# TIC_TAC_PCB1.net
KiCad netlist of a schematic drawn in EAGLE
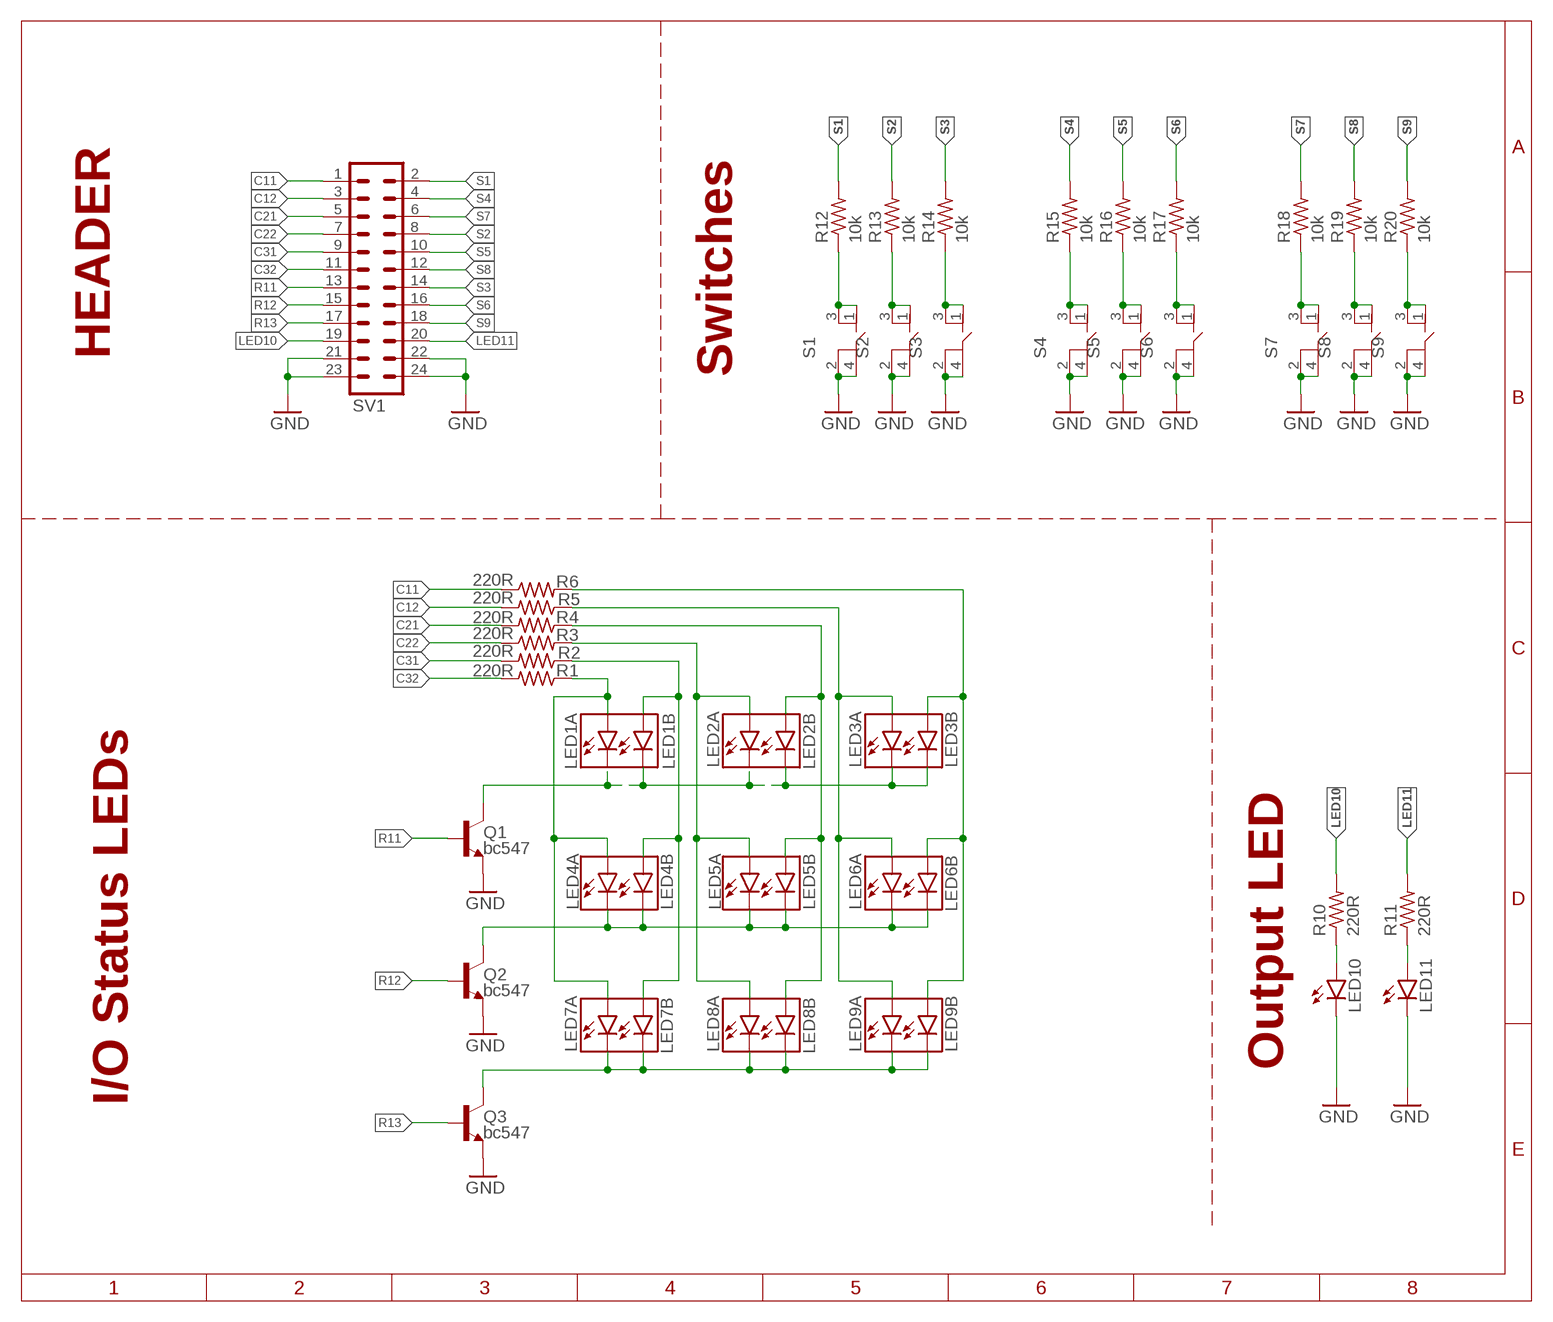
[diagram p0: schematic, sheet 1]

(export (version "E")
  (design (tool "Eeschema 10.0.6"))
  (components
    (comp (ref "LED1A")
      (value "LEDSML0805")
      (footprint "eagle-import:SML0805")
      (libsource (lib "eagle-import") (part "LEDSML0805"))
    )
    (comp (ref "LED1B")
      (value "LEDSML0805")
      (footprint "eagle-import:SML0805")
      (libsource (lib "eagle-import") (part "LEDSML0805"))
    )
    (comp (ref "LED2A")
      (value "LEDSML0805")
      (footprint "eagle-import:SML0805")
      (libsource (lib "eagle-import") (part "LEDSML0805"))
    )
    (comp (ref "LED2B")
      (value "LEDSML0805")
      (footprint "eagle-import:SML0805")
      (libsource (lib "eagle-import") (part "LEDSML0805"))
    )
    (comp (ref "LED3A")
      (value "LEDSML0805")
      (footprint "eagle-import:SML0805")
      (libsource (lib "eagle-import") (part "LEDSML0805"))
    )
    (comp (ref "LED3B")
      (value "LEDSML0805")
      (footprint "eagle-import:SML0805")
      (libsource (lib "eagle-import") (part "LEDSML0805"))
    )
    (comp (ref "LED4A")
      (value "LEDSML0805")
      (footprint "eagle-import:SML0805")
      (libsource (lib "eagle-import") (part "LEDSML0805"))
    )
    (comp (ref "LED4B")
      (value "LEDSML0805")
      (footprint "eagle-import:SML0805")
      (libsource (lib "eagle-import") (part "LEDSML0805"))
    )
    (comp (ref "LED5A")
      (value "LEDSML0805")
      (footprint "eagle-import:SML0805")
      (libsource (lib "eagle-import") (part "LEDSML0805"))
    )
    (comp (ref "LED5B")
      (value "LEDSML0805")
      (footprint "eagle-import:SML0805")
      (libsource (lib "eagle-import") (part "LEDSML0805"))
    )
    (comp (ref "LED6A")
      (value "LEDSML0805")
      (footprint "eagle-import:SML0805")
      (libsource (lib "eagle-import") (part "LEDSML0805"))
    )
    (comp (ref "LED6B")
      (value "LEDSML0805")
      (footprint "eagle-import:SML0805")
      (libsource (lib "eagle-import") (part "LEDSML0805"))
    )
    (comp (ref "LED7A")
      (value "LEDSML0805")
      (footprint "eagle-import:SML0805")
      (libsource (lib "eagle-import") (part "LEDSML0805"))
    )
    (comp (ref "LED7B")
      (value "LEDSML0805")
      (footprint "eagle-import:SML0805")
      (libsource (lib "eagle-import") (part "LEDSML0805"))
    )
    (comp (ref "LED8A")
      (value "LEDSML0805")
      (footprint "eagle-import:SML0805")
      (libsource (lib "eagle-import") (part "LEDSML0805"))
    )
    (comp (ref "LED8B")
      (value "LEDSML0805")
      (footprint "eagle-import:SML0805")
      (libsource (lib "eagle-import") (part "LEDSML0805"))
    )
    (comp (ref "LED9A")
      (value "LEDSML0805")
      (footprint "eagle-import:SML0805")
      (libsource (lib "eagle-import") (part "LEDSML0805"))
    )
    (comp (ref "LED9B")
      (value "LEDSML0805")
      (footprint "eagle-import:SML0805")
      (libsource (lib "eagle-import") (part "LEDSML0805"))
    )
    (comp (ref "LED10")
      (value "LEDSMT1206")
      (footprint "eagle-import:1206")
      (libsource (lib "eagle-import") (part "LEDSMT1206"))
    )
    (comp (ref "LED11")
      (value "LEDSMT1206")
      (footprint "eagle-import:1206")
      (libsource (lib "eagle-import") (part "LEDSMT1206"))
    )
    (comp (ref "Q1")
      (value "bc547")
      (footprint "eagle-import:SOT23-3")
      (libsource (lib "eagle-import") (part "TRANS_NPN-MMBT2222AL"))
    )
    (comp (ref "Q2")
      (value "bc547")
      (footprint "eagle-import:SOT23-3")
      (libsource (lib "eagle-import") (part "TRANS_NPN-MMBT2222AL"))
    )
    (comp (ref "Q3")
      (value "bc547")
      (footprint "eagle-import:SOT23-3")
      (libsource (lib "eagle-import") (part "TRANS_NPN-MMBT2222AL"))
    )
    (comp (ref "R1")
      (value "220R")
      (footprint "eagle-import:M0805")
      (libsource (lib "eagle-import") (part "R-US_M0805"))
    )
    (comp (ref "R2")
      (value "220R")
      (footprint "eagle-import:M0805")
      (libsource (lib "eagle-import") (part "R-US_M0805"))
    )
    (comp (ref "R3")
      (value "220R")
      (footprint "eagle-import:M0805")
      (libsource (lib "eagle-import") (part "R-US_M0805"))
    )
    (comp (ref "R4")
      (value "220R")
      (footprint "eagle-import:M0805")
      (libsource (lib "eagle-import") (part "R-US_M0805"))
    )
    (comp (ref "R5")
      (value "220R")
      (footprint "eagle-import:M0805")
      (libsource (lib "eagle-import") (part "R-US_M0805"))
    )
    (comp (ref "R6")
      (value "220R")
      (footprint "eagle-import:M0805")
      (libsource (lib "eagle-import") (part "R-US_M0805"))
    )
    (comp (ref "R10")
      (value "220R")
      (footprint "eagle-import:M0805")
      (libsource (lib "eagle-import") (part "R-US_M0805"))
    )
    (comp (ref "R11")
      (value "220R")
      (footprint "eagle-import:M0805")
      (libsource (lib "eagle-import") (part "R-US_M0805"))
    )
    (comp (ref "R12")
      (value "10k")
      (footprint "eagle-import:M0805")
      (libsource (lib "eagle-import") (part "R-US_M0805"))
    )
    (comp (ref "R13")
      (value "10k")
      (footprint "eagle-import:M0805")
      (libsource (lib "eagle-import") (part "R-US_M0805"))
    )
    (comp (ref "R14")
      (value "10k")
      (footprint "eagle-import:M0805")
      (libsource (lib "eagle-import") (part "R-US_M0805"))
    )
    (comp (ref "R15")
      (value "10k")
      (footprint "eagle-import:M0805")
      (libsource (lib "eagle-import") (part "R-US_M0805"))
    )
    (comp (ref "R16")
      (value "10k")
      (footprint "eagle-import:M0805")
      (libsource (lib "eagle-import") (part "R-US_M0805"))
    )
    (comp (ref "R17")
      (value "10k")
      (footprint "eagle-import:M0805")
      (libsource (lib "eagle-import") (part "R-US_M0805"))
    )
    (comp (ref "R18")
      (value "10k")
      (footprint "eagle-import:M0805")
      (libsource (lib "eagle-import") (part "R-US_M0805"))
    )
    (comp (ref "R19")
      (value "10k")
      (footprint "eagle-import:M0805")
      (libsource (lib "eagle-import") (part "R-US_M0805"))
    )
    (comp (ref "R20")
      (value "10k")
      (footprint "eagle-import:M0805")
      (libsource (lib "eagle-import") (part "R-US_M0805"))
    )
    (comp (ref "S1")
      (value "TS04-66-95-BK-100-SMT")
      (footprint "eagle-import:SW_TS04-66-95-BK-100-SMT")
      (fields (field (name "MF") "CUI Devices"))
      (libsource (lib "eagle-import") (part "TS04-66-95-BK-100-SMT"))
    )
    (comp (ref "S2")
      (value "TS04-66-95-BK-100-SMT")
      (footprint "eagle-import:SW_TS04-66-95-BK-100-SMT")
      (fields (field (name "MF") "CUI Devices"))
      (libsource (lib "eagle-import") (part "TS04-66-95-BK-100-SMT"))
    )
    (comp (ref "S3")
      (value "TS04-66-95-BK-100-SMT")
      (footprint "eagle-import:SW_TS04-66-95-BK-100-SMT")
      (fields (field (name "MF") "CUI Devices"))
      (libsource (lib "eagle-import") (part "TS04-66-95-BK-100-SMT"))
    )
    (comp (ref "S4")
      (value "TS04-66-95-BK-100-SMT")
      (footprint "eagle-import:SW_TS04-66-95-BK-100-SMT")
      (fields (field (name "MF") "CUI Devices"))
      (libsource (lib "eagle-import") (part "TS04-66-95-BK-100-SMT"))
    )
    (comp (ref "S5")
      (value "TS04-66-95-BK-100-SMT")
      (footprint "eagle-import:SW_TS04-66-95-BK-100-SMT")
      (fields (field (name "MF") "CUI Devices"))
      (libsource (lib "eagle-import") (part "TS04-66-95-BK-100-SMT"))
    )
    (comp (ref "S6")
      (value "TS04-66-95-BK-100-SMT")
      (footprint "eagle-import:SW_TS04-66-95-BK-100-SMT")
      (fields (field (name "MF") "CUI Devices"))
      (libsource (lib "eagle-import") (part "TS04-66-95-BK-100-SMT"))
    )
    (comp (ref "S7")
      (value "TS04-66-95-BK-100-SMT")
      (footprint "eagle-import:SW_TS04-66-95-BK-100-SMT")
      (fields (field (name "MF") "CUI Devices"))
      (libsource (lib "eagle-import") (part "TS04-66-95-BK-100-SMT"))
    )
    (comp (ref "S8")
      (value "TS04-66-95-BK-100-SMT")
      (footprint "eagle-import:SW_TS04-66-95-BK-100-SMT")
      (fields (field (name "MF") "CUI Devices"))
      (libsource (lib "eagle-import") (part "TS04-66-95-BK-100-SMT"))
    )
    (comp (ref "S9")
      (value "TS04-66-95-BK-100-SMT")
      (footprint "eagle-import:SW_TS04-66-95-BK-100-SMT")
      (fields (field (name "MF") "CUI Devices"))
      (libsource (lib "eagle-import") (part "TS04-66-95-BK-100-SMT"))
    )
    (comp (ref "SV1")
      (value "MA12-2")
      (footprint "eagle-import:MA12-2")
      (libsource (lib "eagle-import") (part "MA12-2"))
    )
  )
  (nets
    (net (code "1") (name "C11") (class "Default")
      (node (ref "R6") (pin "1") (pinfunction "1_1") (pintype "passive"))
      (node (ref "SV1") (pin "1") (pinfunction "1_1") (pintype "passive"))
    )
    (net (code "2") (name "C12") (class "Default")
      (node (ref "R5") (pin "2") (pinfunction "2_2") (pintype "passive"))
      (node (ref "SV1") (pin "3") (pinfunction "3_3") (pintype "passive"))
    )
    (net (code "3") (name "C21") (class "Default")
      (node (ref "R4") (pin "2") (pinfunction "2_2") (pintype "passive"))
      (node (ref "SV1") (pin "5") (pinfunction "5_5") (pintype "passive"))
    )
    (net (code "4") (name "C22") (class "Default")
      (node (ref "R3") (pin "1") (pinfunction "1_1") (pintype "passive"))
      (node (ref "SV1") (pin "7") (pinfunction "7_7") (pintype "passive"))
    )
    (net (code "5") (name "C31") (class "Default")
      (node (ref "R2") (pin "2") (pinfunction "2_2") (pintype "passive"))
      (node (ref "SV1") (pin "9") (pinfunction "9_9") (pintype "passive"))
    )
    (net (code "6") (name "C32") (class "Default")
      (node (ref "R1") (pin "2") (pinfunction "2_2") (pintype "passive"))
      (node (ref "SV1") (pin "11") (pinfunction "11_11") (pintype "passive"))
    )
    (net (code "7") (name "GND") (class "Default")
      (node (ref "LED10") (pin "C") (pinfunction "C_C") (pintype "passive"))
      (node (ref "LED11") (pin "C") (pinfunction "C_C") (pintype "passive"))
      (node (ref "Q1") (pin "2") (pinfunction "E_2") (pintype "passive"))
      (node (ref "Q2") (pin "2") (pinfunction "E_2") (pintype "passive"))
      (node (ref "Q3") (pin "2") (pinfunction "E_2") (pintype "passive"))
      (node (ref "S1") (pin "2") (pinfunction "3_2") (pintype "passive"))
      (node (ref "S1") (pin "4") (pinfunction "4_4") (pintype "passive"))
      (node (ref "S2") (pin "2") (pinfunction "3_2") (pintype "passive"))
      (node (ref "S2") (pin "4") (pinfunction "4_4") (pintype "passive"))
      (node (ref "S3") (pin "2") (pinfunction "3_2") (pintype "passive"))
      (node (ref "S3") (pin "4") (pinfunction "4_4") (pintype "passive"))
      (node (ref "S4") (pin "2") (pinfunction "3_2") (pintype "passive"))
      (node (ref "S4") (pin "4") (pinfunction "4_4") (pintype "passive"))
      (node (ref "S5") (pin "2") (pinfunction "3_2") (pintype "passive"))
      (node (ref "S5") (pin "4") (pinfunction "4_4") (pintype "passive"))
      (node (ref "S6") (pin "2") (pinfunction "3_2") (pintype "passive"))
      (node (ref "S6") (pin "4") (pinfunction "4_4") (pintype "passive"))
      (node (ref "S7") (pin "2") (pinfunction "3_2") (pintype "passive"))
      (node (ref "S7") (pin "4") (pinfunction "4_4") (pintype "passive"))
      (node (ref "S8") (pin "2") (pinfunction "3_2") (pintype "passive"))
      (node (ref "S8") (pin "4") (pinfunction "4_4") (pintype "passive"))
      (node (ref "S9") (pin "2") (pinfunction "3_2") (pintype "passive"))
      (node (ref "S9") (pin "4") (pinfunction "4_4") (pintype "passive"))
      (node (ref "SV1") (pin "21") (pinfunction "21_21") (pintype "passive"))
      (node (ref "SV1") (pin "22") (pinfunction "22_22") (pintype "passive"))
      (node (ref "SV1") (pin "23") (pinfunction "23_23") (pintype "passive"))
      (node (ref "SV1") (pin "24") (pinfunction "24_24") (pintype "passive"))
    )
    (net (code "8") (name "LED10") (class "Default")
      (node (ref "R10") (pin "2") (pinfunction "2_2") (pintype "passive"))
      (node (ref "SV1") (pin "19") (pinfunction "19_19") (pintype "passive"))
    )
    (net (code "9") (name "LED11") (class "Default")
      (node (ref "R11") (pin "2") (pinfunction "2_2") (pintype "passive"))
      (node (ref "SV1") (pin "20") (pinfunction "20_20") (pintype "passive"))
    )
    (net (code "10") (name "Net-(LED1A-PadA)") (class "Default")
      (node (ref "LED1A") (pin "A") (pinfunction "A_A") (pintype "passive"))
      (node (ref "LED4A") (pin "A") (pinfunction "A_A") (pintype "passive"))
      (node (ref "LED7A") (pin "A") (pinfunction "A_A") (pintype "passive"))
      (node (ref "R1") (pin "1") (pinfunction "1_1") (pintype "passive"))
    )
    (net (code "11") (name "Net-(LED1B-PadA)") (class "Default")
      (node (ref "LED1B") (pin "A") (pinfunction "A_A") (pintype "passive"))
      (node (ref "LED4B") (pin "A") (pinfunction "A_A") (pintype "passive"))
      (node (ref "LED7B") (pin "A") (pinfunction "A_A") (pintype "passive"))
      (node (ref "R2") (pin "1") (pinfunction "1_1") (pintype "passive"))
    )
    (net (code "12") (name "Net-(LED2A-PadA)") (class "Default")
      (node (ref "LED2A") (pin "A") (pinfunction "A_A") (pintype "passive"))
      (node (ref "LED5A") (pin "A") (pinfunction "A_A") (pintype "passive"))
      (node (ref "LED8A") (pin "A") (pinfunction "A_A") (pintype "passive"))
      (node (ref "R3") (pin "2") (pinfunction "2_2") (pintype "passive"))
    )
    (net (code "13") (name "Net-(LED2B-PadA)") (class "Default")
      (node (ref "LED2B") (pin "A") (pinfunction "A_A") (pintype "passive"))
      (node (ref "LED5B") (pin "A") (pinfunction "A_A") (pintype "passive"))
      (node (ref "LED8B") (pin "A") (pinfunction "A_A") (pintype "passive"))
      (node (ref "R4") (pin "1") (pinfunction "1_1") (pintype "passive"))
    )
    (net (code "14") (name "Net-(LED3A-PadA)") (class "Default")
      (node (ref "LED3A") (pin "A") (pinfunction "A_A") (pintype "passive"))
      (node (ref "LED6A") (pin "A") (pinfunction "A_A") (pintype "passive"))
      (node (ref "LED9A") (pin "A") (pinfunction "A_A") (pintype "passive"))
      (node (ref "R5") (pin "1") (pinfunction "1_1") (pintype "passive"))
    )
    (net (code "15") (name "Net-(LED3B-PadA)") (class "Default")
      (node (ref "LED3B") (pin "A") (pinfunction "A_A") (pintype "passive"))
      (node (ref "LED6B") (pin "A") (pinfunction "A_A") (pintype "passive"))
      (node (ref "LED9B") (pin "A") (pinfunction "A_A") (pintype "passive"))
      (node (ref "R6") (pin "2") (pinfunction "2_2") (pintype "passive"))
    )
    (net (code "16") (name "Net-(LED10-PadA)") (class "Default")
      (node (ref "LED10") (pin "A") (pinfunction "A_A") (pintype "passive"))
      (node (ref "R10") (pin "1") (pinfunction "1_1") (pintype "passive"))
    )
    (net (code "17") (name "Net-(LED11-PadA)") (class "Default")
      (node (ref "LED11") (pin "A") (pinfunction "A_A") (pintype "passive"))
      (node (ref "R11") (pin "1") (pinfunction "1_1") (pintype "passive"))
    )
    (net (code "18") (name "Net-(Q1-C)") (class "Default")
      (node (ref "LED1A") (pin "C") (pinfunction "C_C") (pintype "passive"))
      (node (ref "LED1B") (pin "C") (pinfunction "C_C") (pintype "passive"))
      (node (ref "LED2A") (pin "C") (pinfunction "C_C") (pintype "passive"))
      (node (ref "LED2B") (pin "C") (pinfunction "C_C") (pintype "passive"))
      (node (ref "LED3A") (pin "C") (pinfunction "C_C") (pintype "passive"))
      (node (ref "LED3B") (pin "C") (pinfunction "C_C") (pintype "passive"))
      (node (ref "Q1") (pin "3") (pinfunction "C_3") (pintype "passive"))
    )
    (net (code "19") (name "Net-(Q2-C)") (class "Default")
      (node (ref "LED4A") (pin "C") (pinfunction "C_C") (pintype "passive"))
      (node (ref "LED4B") (pin "C") (pinfunction "C_C") (pintype "passive"))
      (node (ref "LED5A") (pin "C") (pinfunction "C_C") (pintype "passive"))
      (node (ref "LED5B") (pin "C") (pinfunction "C_C") (pintype "passive"))
      (node (ref "LED6A") (pin "C") (pinfunction "C_C") (pintype "passive"))
      (node (ref "LED6B") (pin "C") (pinfunction "C_C") (pintype "passive"))
      (node (ref "Q2") (pin "3") (pinfunction "C_3") (pintype "passive"))
    )
    (net (code "20") (name "Net-(Q3-C)") (class "Default")
      (node (ref "LED7A") (pin "C") (pinfunction "C_C") (pintype "passive"))
      (node (ref "LED7B") (pin "C") (pinfunction "C_C") (pintype "passive"))
      (node (ref "LED8A") (pin "C") (pinfunction "C_C") (pintype "passive"))
      (node (ref "LED8B") (pin "C") (pinfunction "C_C") (pintype "passive"))
      (node (ref "LED9A") (pin "C") (pinfunction "C_C") (pintype "passive"))
      (node (ref "LED9B") (pin "C") (pinfunction "C_C") (pintype "passive"))
      (node (ref "Q3") (pin "3") (pinfunction "C_3") (pintype "passive"))
    )
    (net (code "21") (name "Net-(S1-2)") (class "Default")
      (node (ref "R12") (pin "1") (pinfunction "1_1") (pintype "passive"))
      (node (ref "S1") (pin "1") (pinfunction "1_1") (pintype "passive"))
      (node (ref "S1") (pin "3") (pinfunction "2_3") (pintype "passive"))
    )
    (net (code "22") (name "Net-(S2-2)") (class "Default")
      (node (ref "R13") (pin "1") (pinfunction "1_1") (pintype "passive"))
      (node (ref "S2") (pin "1") (pinfunction "1_1") (pintype "passive"))
      (node (ref "S2") (pin "3") (pinfunction "2_3") (pintype "passive"))
    )
    (net (code "23") (name "Net-(S3-2)") (class "Default")
      (node (ref "R14") (pin "1") (pinfunction "1_1") (pintype "passive"))
      (node (ref "S3") (pin "1") (pinfunction "1_1") (pintype "passive"))
      (node (ref "S3") (pin "3") (pinfunction "2_3") (pintype "passive"))
    )
    (net (code "24") (name "Net-(S4-2)") (class "Default")
      (node (ref "R15") (pin "1") (pinfunction "1_1") (pintype "passive"))
      (node (ref "S4") (pin "1") (pinfunction "1_1") (pintype "passive"))
      (node (ref "S4") (pin "3") (pinfunction "2_3") (pintype "passive"))
    )
    (net (code "25") (name "Net-(S5-2)") (class "Default")
      (node (ref "R16") (pin "1") (pinfunction "1_1") (pintype "passive"))
      (node (ref "S5") (pin "1") (pinfunction "1_1") (pintype "passive"))
      (node (ref "S5") (pin "3") (pinfunction "2_3") (pintype "passive"))
    )
    (net (code "26") (name "Net-(S6-2)") (class "Default")
      (node (ref "R17") (pin "1") (pinfunction "1_1") (pintype "passive"))
      (node (ref "S6") (pin "1") (pinfunction "1_1") (pintype "passive"))
      (node (ref "S6") (pin "3") (pinfunction "2_3") (pintype "passive"))
    )
    (net (code "27") (name "Net-(S7-2)") (class "Default")
      (node (ref "R18") (pin "1") (pinfunction "1_1") (pintype "passive"))
      (node (ref "S7") (pin "1") (pinfunction "1_1") (pintype "passive"))
      (node (ref "S7") (pin "3") (pinfunction "2_3") (pintype "passive"))
    )
    (net (code "28") (name "Net-(S8-2)") (class "Default")
      (node (ref "R19") (pin "1") (pinfunction "1_1") (pintype "passive"))
      (node (ref "S8") (pin "1") (pinfunction "1_1") (pintype "passive"))
      (node (ref "S8") (pin "3") (pinfunction "2_3") (pintype "passive"))
    )
    (net (code "29") (name "Net-(S9-2)") (class "Default")
      (node (ref "R20") (pin "1") (pinfunction "1_1") (pintype "passive"))
      (node (ref "S9") (pin "1") (pinfunction "1_1") (pintype "passive"))
      (node (ref "S9") (pin "3") (pinfunction "2_3") (pintype "passive"))
    )
    (net (code "30") (name "R11") (class "Default")
      (node (ref "Q1") (pin "1") (pinfunction "B_1") (pintype "passive"))
      (node (ref "SV1") (pin "13") (pinfunction "13_13") (pintype "passive"))
    )
    (net (code "31") (name "R12") (class "Default")
      (node (ref "Q2") (pin "1") (pinfunction "B_1") (pintype "passive"))
      (node (ref "SV1") (pin "15") (pinfunction "15_15") (pintype "passive"))
    )
    (net (code "32") (name "R13") (class "Default")
      (node (ref "Q3") (pin "1") (pinfunction "B_1") (pintype "passive"))
      (node (ref "SV1") (pin "17") (pinfunction "17_17") (pintype "passive"))
    )
    (net (code "33") (name "S1") (class "Default")
      (node (ref "R12") (pin "2") (pinfunction "2_2") (pintype "passive"))
      (node (ref "SV1") (pin "2") (pinfunction "2_2") (pintype "passive"))
    )
    (net (code "34") (name "S2") (class "Default")
      (node (ref "R13") (pin "2") (pinfunction "2_2") (pintype "passive"))
      (node (ref "SV1") (pin "8") (pinfunction "8_8") (pintype "passive"))
    )
    (net (code "35") (name "S3") (class "Default")
      (node (ref "R14") (pin "2") (pinfunction "2_2") (pintype "passive"))
      (node (ref "SV1") (pin "14") (pinfunction "14_14") (pintype "passive"))
    )
    (net (code "36") (name "S4") (class "Default")
      (node (ref "R15") (pin "2") (pinfunction "2_2") (pintype "passive"))
      (node (ref "SV1") (pin "4") (pinfunction "4_4") (pintype "passive"))
    )
    (net (code "37") (name "S5") (class "Default")
      (node (ref "R16") (pin "2") (pinfunction "2_2") (pintype "passive"))
      (node (ref "SV1") (pin "10") (pinfunction "10_10") (pintype "passive"))
    )
    (net (code "38") (name "S6") (class "Default")
      (node (ref "R17") (pin "2") (pinfunction "2_2") (pintype "passive"))
      (node (ref "SV1") (pin "16") (pinfunction "16_16") (pintype "passive"))
    )
    (net (code "39") (name "S7") (class "Default")
      (node (ref "R18") (pin "2") (pinfunction "2_2") (pintype "passive"))
      (node (ref "SV1") (pin "6") (pinfunction "6_6") (pintype "passive"))
    )
    (net (code "40") (name "S8") (class "Default")
      (node (ref "R19") (pin "2") (pinfunction "2_2") (pintype "passive"))
      (node (ref "SV1") (pin "12") (pinfunction "12_12") (pintype "passive"))
    )
    (net (code "41") (name "S9") (class "Default")
      (node (ref "R20") (pin "2") (pinfunction "2_2") (pintype "passive"))
      (node (ref "SV1") (pin "18") (pinfunction "18_18") (pintype "passive"))
    )
  )
)
